# GNSS_modulis.net
KiCad netlist of a schematic drawn in Altium Designer
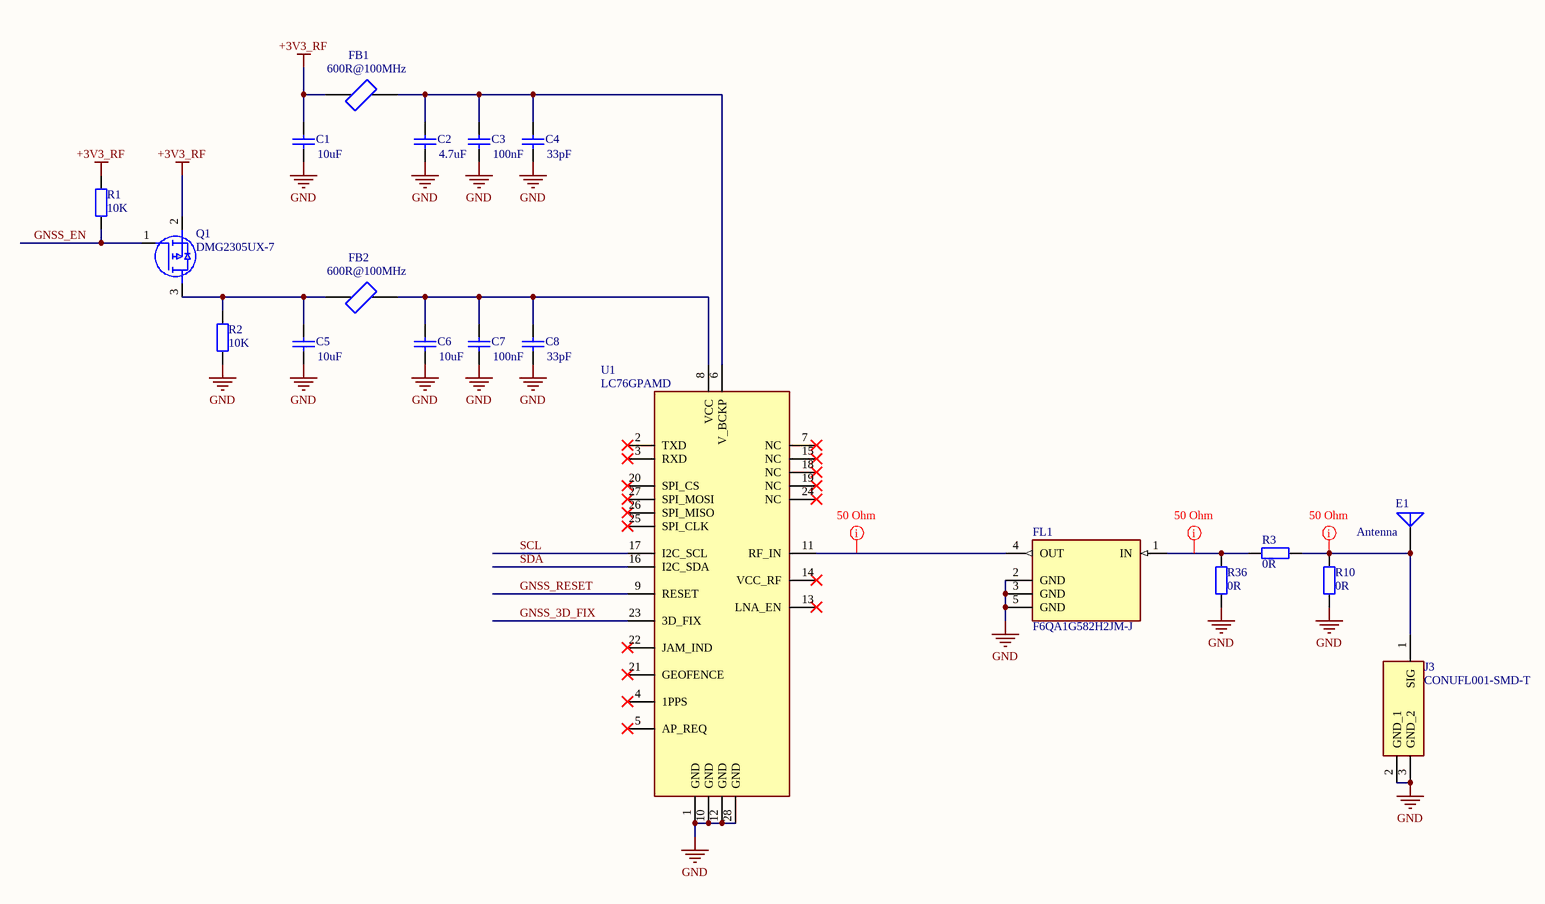
[diagram p0: GNSS modulis.SchDoc]

(export (version "E")
  (design (tool "Eeschema 10.0.6"))
  (components
    (comp (ref "C1")
      (value "10uF")
      (footprint "SMD-0805C")
      (description "Capacitor")
      (fields (field (name "PUBLISHER") "Altium Limited"))
      (libsource (lib "Miscellaneous Devices") (part "Cap"))
    )
    (comp (ref "C2")
      (value "4.7uF")
      (footprint "SMD-0603C")
      (description "Capacitor")
      (fields (field (name "PUBLISHER") "Altium Limited"))
      (libsource (lib "Miscellaneous Devices") (part "Cap"))
    )
    (comp (ref "C3")
      (value "100nF")
      (footprint "SMD-0402C")
      (description "Capacitor")
      (fields (field (name "PUBLISHER") "Altium Limited"))
      (libsource (lib "Miscellaneous Devices") (part "Cap"))
    )
    (comp (ref "C4")
      (value "33pF")
      (footprint "SMD-0402C")
      (description "Capacitor")
      (fields (field (name "PUBLISHER") "Altium Limited"))
      (libsource (lib "Miscellaneous Devices") (part "Cap"))
    )
    (comp (ref "C5")
      (value "10uF")
      (footprint "SMD-0805C")
      (description "Capacitor")
      (fields (field (name "PUBLISHER") "Altium Limited"))
      (libsource (lib "Miscellaneous Devices") (part "Cap"))
    )
    (comp (ref "C6")
      (value "10uF")
      (footprint "SMD-0805C")
      (description "Capacitor")
      (fields (field (name "PUBLISHER") "Altium Limited"))
      (libsource (lib "Miscellaneous Devices") (part "Cap"))
    )
    (comp (ref "C7")
      (value "100nF")
      (footprint "SMD-0402C")
      (description "Capacitor")
      (fields (field (name "PUBLISHER") "Altium Limited"))
      (libsource (lib "Miscellaneous Devices") (part "Cap"))
    )
    (comp (ref "C8")
      (value "33pF")
      (footprint "SMD-0402C")
      (description "Capacitor")
      (fields (field (name "PUBLISHER") "Altium Limited"))
      (libsource (lib "Miscellaneous Devices") (part "Cap"))
    )
    (comp (ref "E1")
      (value "Antenna")
      (footprint "204286-0001_MOL")
      (description "Generic Antenna")
      (fields (field (name "PUBLISHER") "Altium Limited"))
      (libsource (lib "Miscellaneous Devices") (part "Antenna"))
    )
    (comp (ref "FB1")
      (value "600R@100MHz")
      (footprint "0402 Ferrite Bead")
      (description "Ferrite Beads FERRITE BEAD 600 OHM 0402 1LN")
      (fields (field (name "MF") "Laird-Signal Integrity Products") (field (name "MP") "MI0805K400R-10"))
      (libsource (lib "Schematic_library") (part "Ferrite"))
    )
    (comp (ref "FB2")
      (value "600R@100MHz")
      (footprint "0402 Ferrite Bead")
      (description "Ferrite Beads FERRITE BEAD 600 OHM 0402 1LN")
      (fields (field (name "MF") "Laird-Signal Integrity Products") (field (name "MP") "MI0805K400R-10"))
      (libsource (lib "Schematic_library") (part "Ferrite"))
    )
    (comp (ref "FL1")
      (value "F6QA1G582H2JM-J")
      (footprint "FIL_F6QA1G582H2JM-J")
      (description "1.582GHz Frequency GPS RF SAW Filter (Surface Acoustic Wave) 1.8dB  Bandwidth 5-SMD, No Lead")
      (fields (field (name "MF") "Taiyo Yuden"))
      (libsource (lib "Schematic_library") (part "F6QA1G582H2JM-J"))
    )
    (comp (ref "J3")
      (value "CONUFL001-SMD-T")
      (footprint "SamacSys:CONUFL001SMDT")
      (description "Connector")
      (libsource (lib "Schematic_library") (part "CONUFL001-SMD-T"))
    )
    (comp (ref "Q1")
      (value "DMG2305UX-7")
      (footprint "DMG2305UX-7")
      (fields (field (name "MOUSER PART NUMBER") "621-DMG2305UX-7"))
      (libsource (lib "Schematic_library") (part "DMG2305UX-7"))
    )
    (comp (ref "R1")
      (value "10K")
      (footprint "SMD-0402-RES")
      (description "Resistor")
      (fields (field (name "PUBLISHER") "Altium Limited"))
      (libsource (lib "Miscellaneous Devices") (part "Res2"))
    )
    (comp (ref "R2")
      (value "10K")
      (footprint "SMD-0402-RES")
      (description "Resistor")
      (fields (field (name "PUBLISHER") "Altium Limited"))
      (libsource (lib "Miscellaneous Devices") (part "Res2"))
    )
    (comp (ref "R3")
      (value "0R")
      (footprint "SMD-0402-RES")
      (description "Resistor")
      (fields (field (name "PUBLISHER") "Altium Limited"))
      (libsource (lib "") (part "Res2_1"))
    )
    (comp (ref "R10")
      (value "0R")
      (footprint "SMD-0402-RES")
      (description "Resistor")
      (fields (field (name "PUBLISHER") "Altium Limited"))
      (libsource (lib "Miscellaneous Devices") (part "Res2"))
    )
    (comp (ref "R36")
      (value "0R")
      (footprint "SMD-0402-RES")
      (description "Resistor")
      (fields (field (name "PUBLISHER") "Altium Limited"))
      (libsource (lib "Miscellaneous Devices") (part "Res2"))
    )
    (comp (ref "U1")
      (value "LC76GPAMD")
      (footprint "SamacSys:LC76GPAMD")
      (fields (field (name "MOUSER PART NUMBER") "277-LC76GPAMD"))
      (libsource (lib "Schematic_library") (part "LC76GPAMD"))
    )
  )
  (nets
    (net (code "1") (name "+3V3_RF") (class "Default")
      (node (ref "C1") (pin "2") (pinfunction "2_2") (pintype "passive"))
      (node (ref "FB1") (pin "1") (pinfunction "1_1") (pintype "passive"))
      (node (ref "Q1") (pin "2") (pinfunction "S_2") (pintype "passive"))
      (node (ref "R1") (pin "2") (pinfunction "2_2") (pintype "passive"))
    )
    (net (code "2") (name "/GNSS_3D_FIX") (class "Default")
      (node (ref "U1") (pin "23") (pinfunction "3D_FIX_23") (pintype "passive"))
    )
    (net (code "3") (name "/GNSS_EN") (class "Default")
      (node (ref "Q1") (pin "1") (pinfunction "G_1") (pintype "passive"))
      (node (ref "R1") (pin "1") (pinfunction "1_1") (pintype "passive"))
    )
    (net (code "4") (name "/GNSS_RESET") (class "Default")
      (node (ref "U1") (pin "9") (pinfunction "RESET_9") (pintype "passive"))
    )
    (net (code "5") (name "/SCL") (class "Default")
      (node (ref "U1") (pin "17") (pinfunction "I2C_SCL_17") (pintype "passive"))
    )
    (net (code "6") (name "/SDA") (class "Default")
      (node (ref "U1") (pin "16") (pinfunction "I2C_SDA_16") (pintype "passive"))
    )
    (net (code "7") (name "GND") (class "Default")
      (node (ref "C1") (pin "1") (pinfunction "1_1") (pintype "passive"))
      (node (ref "C2") (pin "1") (pinfunction "1_1") (pintype "passive"))
      (node (ref "C3") (pin "1") (pinfunction "1_1") (pintype "passive"))
      (node (ref "C4") (pin "1") (pinfunction "1_1") (pintype "passive"))
      (node (ref "C5") (pin "1") (pinfunction "1_1") (pintype "passive"))
      (node (ref "C6") (pin "1") (pinfunction "1_1") (pintype "passive"))
      (node (ref "C7") (pin "1") (pinfunction "1_1") (pintype "passive"))
      (node (ref "C8") (pin "1") (pinfunction "1_1") (pintype "passive"))
      (node (ref "FL1") (pin "2") (pinfunction "GND_2") (pintype "power_in"))
      (node (ref "FL1") (pin "3") (pinfunction "GND_3") (pintype "power_in"))
      (node (ref "FL1") (pin "5") (pinfunction "GND_5") (pintype "power_in"))
      (node (ref "J3") (pin "2") (pinfunction "GND_1_2") (pintype "passive"))
      (node (ref "J3") (pin "3") (pinfunction "GND_2_3") (pintype "passive"))
      (node (ref "R10") (pin "1") (pinfunction "1_1") (pintype "passive"))
      (node (ref "R2") (pin "1") (pinfunction "1_1") (pintype "passive"))
      (node (ref "R36") (pin "1") (pinfunction "1_1") (pintype "passive"))
      (node (ref "U1") (pin "1") (pinfunction "GND_1") (pintype "passive"))
      (node (ref "U1") (pin "10") (pinfunction "GND_10") (pintype "passive"))
      (node (ref "U1") (pin "12") (pinfunction "GND_12") (pintype "passive"))
      (node (ref "U1") (pin "28") (pinfunction "GND_28") (pintype "passive"))
    )
    (net (code "8") (name "Net-(E1-A)") (class "Default")
      (node (ref "E1") (pin "1") (pinfunction "A_1") (pintype "passive"))
      (node (ref "J3") (pin "1") (pinfunction "SIG_1") (pintype "passive"))
      (node (ref "R10") (pin "2") (pinfunction "2_2") (pintype "passive"))
      (node (ref "R3") (pin "1") (pinfunction "1_1") (pintype "passive"))
    )
    (net (code "9") (name "Net-(FL1-IN)") (class "Default")
      (node (ref "FL1") (pin "1") (pinfunction "IN_1") (pintype "input"))
      (node (ref "R3") (pin "2") (pinfunction "2_2") (pintype "passive"))
      (node (ref "R36") (pin "2") (pinfunction "2_2") (pintype "passive"))
    )
    (net (code "10") (name "Net-(FL1-OUT)") (class "Default")
      (node (ref "FL1") (pin "4") (pinfunction "OUT_4") (pintype "output"))
      (node (ref "U1") (pin "11") (pinfunction "RF_IN_11") (pintype "passive"))
    )
    (net (code "11") (name "Net-(Q1-D)") (class "Default")
      (node (ref "C5") (pin "2") (pinfunction "2_2") (pintype "passive"))
      (node (ref "FB2") (pin "1") (pinfunction "1_1") (pintype "passive"))
      (node (ref "Q1") (pin "3") (pinfunction "D_3") (pintype "passive"))
      (node (ref "R2") (pin "2") (pinfunction "2_2") (pintype "passive"))
    )
    (net (code "12") (name "Net-(U1-VCC)") (class "Default")
      (node (ref "C6") (pin "2") (pinfunction "2_2") (pintype "passive"))
      (node (ref "C7") (pin "2") (pinfunction "2_2") (pintype "passive"))
      (node (ref "C8") (pin "2") (pinfunction "2_2") (pintype "passive"))
      (node (ref "FB2") (pin "2") (pinfunction "2_2") (pintype "passive"))
      (node (ref "U1") (pin "8") (pinfunction "VCC_8") (pintype "passive"))
    )
    (net (code "13") (name "Net-(U1-V_BCKP)") (class "Default")
      (node (ref "C2") (pin "2") (pinfunction "2_2") (pintype "passive"))
      (node (ref "C3") (pin "2") (pinfunction "2_2") (pintype "passive"))
      (node (ref "C4") (pin "2") (pinfunction "2_2") (pintype "passive"))
      (node (ref "FB1") (pin "2") (pinfunction "2_2") (pintype "passive"))
      (node (ref "U1") (pin "6") (pinfunction "V_BCKP_6") (pintype "passive"))
    )
    (net (code "14") (name "unconnected-(U1-1PPS-Pad4)") (class "Default")
      (node (ref "U1") (pin "4") (pinfunction "1PPS_4") (pintype "passive+no_connect"))
    )
    (net (code "15") (name "unconnected-(U1-AP_REQ-Pad5)") (class "Default")
      (node (ref "U1") (pin "5") (pinfunction "AP_REQ_5") (pintype "passive+no_connect"))
    )
    (net (code "16") (name "unconnected-(U1-GEOFENCE-Pad21)") (class "Default")
      (node (ref "U1") (pin "21") (pinfunction "GEOFENCE_21") (pintype "passive+no_connect"))
    )
    (net (code "17") (name "unconnected-(U1-JAM_IND-Pad22)") (class "Default")
      (node (ref "U1") (pin "22") (pinfunction "JAM_IND_22") (pintype "passive+no_connect"))
    )
    (net (code "18") (name "unconnected-(U1-LNA_EN-Pad13)") (class "Default")
      (node (ref "U1") (pin "13") (pinfunction "LNA_EN_13") (pintype "passive+no_connect"))
    )
    (net (code "19") (name "unconnected-(U1-NC-Pad7)") (class "Default")
      (node (ref "U1") (pin "7") (pinfunction "NC_7") (pintype "passive+no_connect"))
    )
    (net (code "20") (name "unconnected-(U1-NC-Pad15)") (class "Default")
      (node (ref "U1") (pin "15") (pinfunction "NC_15") (pintype "passive+no_connect"))
    )
    (net (code "21") (name "unconnected-(U1-NC-Pad18)") (class "Default")
      (node (ref "U1") (pin "18") (pinfunction "NC_18") (pintype "passive+no_connect"))
    )
    (net (code "22") (name "unconnected-(U1-NC-Pad19)") (class "Default")
      (node (ref "U1") (pin "19") (pinfunction "NC_19") (pintype "passive+no_connect"))
    )
    (net (code "23") (name "unconnected-(U1-NC-Pad24)") (class "Default")
      (node (ref "U1") (pin "24") (pinfunction "NC_24") (pintype "passive+no_connect"))
    )
    (net (code "24") (name "unconnected-(U1-RXD-Pad3)") (class "Default")
      (node (ref "U1") (pin "3") (pinfunction "RXD_3") (pintype "passive+no_connect"))
    )
    (net (code "25") (name "unconnected-(U1-SPI_CLK-Pad25)") (class "Default")
      (node (ref "U1") (pin "25") (pinfunction "SPI_CLK_25") (pintype "passive+no_connect"))
    )
    (net (code "26") (name "unconnected-(U1-SPI_CS-Pad20)") (class "Default")
      (node (ref "U1") (pin "20") (pinfunction "SPI_CS_20") (pintype "passive+no_connect"))
    )
    (net (code "27") (name "unconnected-(U1-SPI_MISO-Pad26)") (class "Default")
      (node (ref "U1") (pin "26") (pinfunction "SPI_MISO_26") (pintype "passive+no_connect"))
    )
    (net (code "28") (name "unconnected-(U1-SPI_MOSI-Pad27)") (class "Default")
      (node (ref "U1") (pin "27") (pinfunction "SPI_MOSI_27") (pintype "passive+no_connect"))
    )
    (net (code "29") (name "unconnected-(U1-TXD-Pad2)") (class "Default")
      (node (ref "U1") (pin "2") (pinfunction "TXD_2") (pintype "passive+no_connect"))
    )
    (net (code "30") (name "unconnected-(U1-VCC_RF-Pad14)") (class "Default")
      (node (ref "U1") (pin "14") (pinfunction "VCC_RF_14") (pintype "passive+no_connect"))
    )
  )
)
